# proLAYOUT.net
KiCad netlist of a schematic drawn in Altium Designer
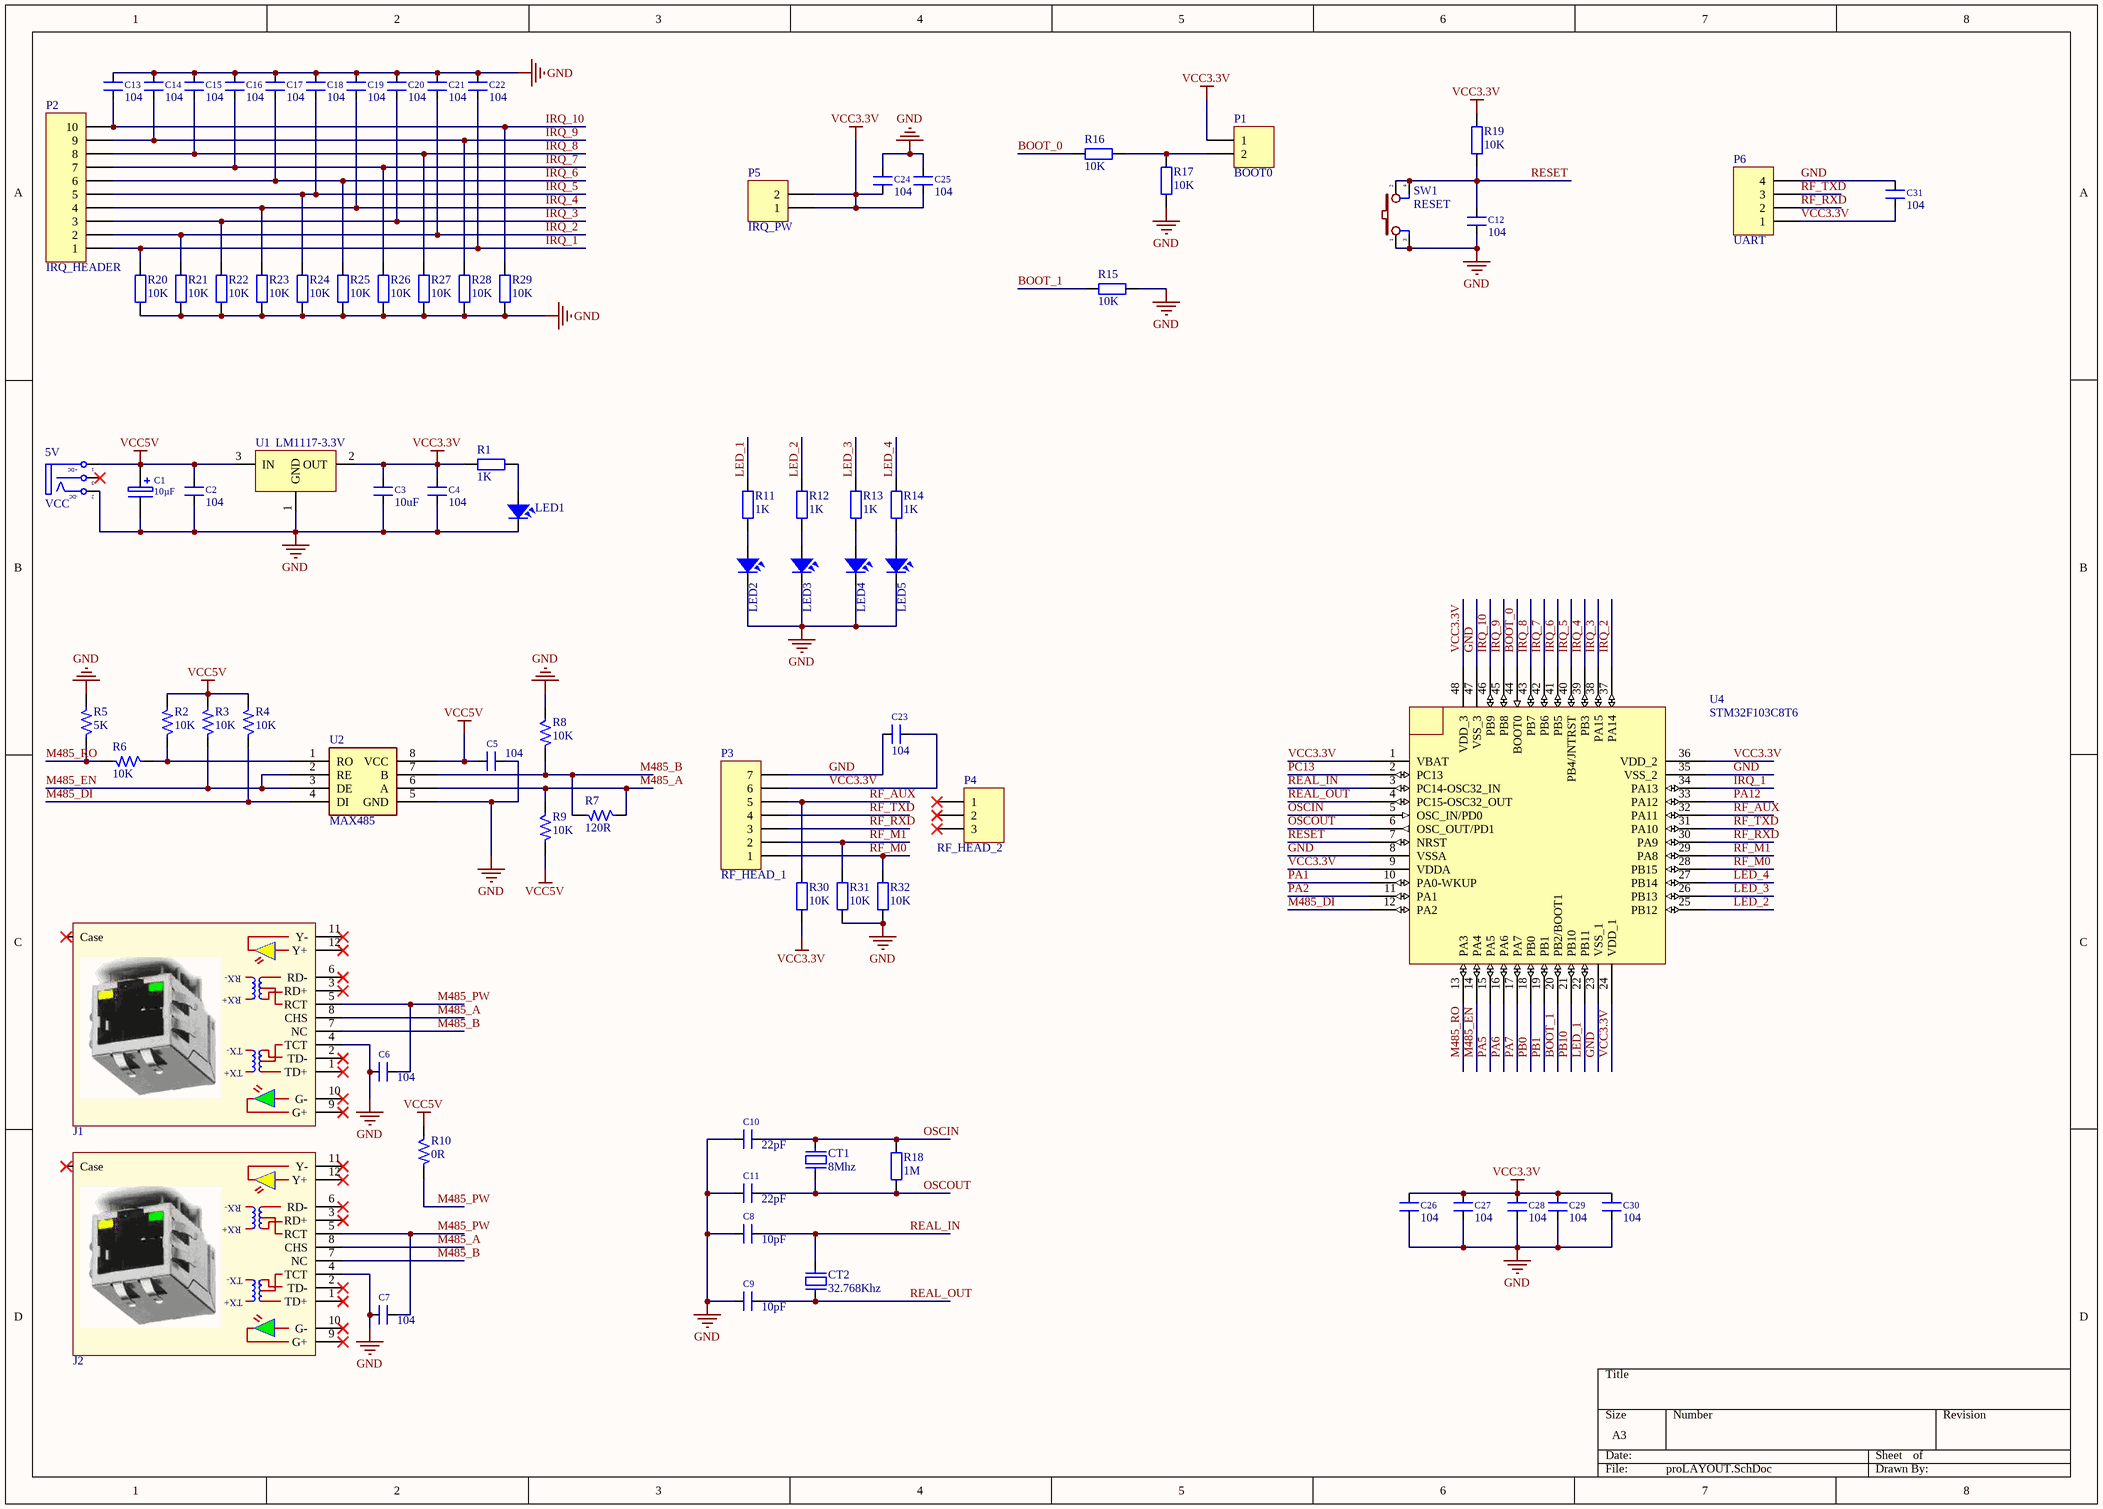
[diagram p0: proLAYOUT.SchDoc]

(export (version "E")
  (design (tool "Eeschema 10.0.6"))
  (components
    (comp (ref "C1")
      (value "10µF")
      (footprint "CAP_ELEC_5x5.7")
      (fields (field (name "ALTIUM_UNNAMED_1") "10µF"))
      (libsource (lib "My library altium") (part "CAP Aluminum"))
    )
    (comp (ref "C2")
      (value "104")
      (footprint "SM-CAP-0805")
      (fields (field (name "DESIGNED BY") "VanDungEvn"))
      (libsource (lib "My library altium") (part "CAP SMD"))
    )
    (comp (ref "C3")
      (value "10uF")
      (footprint "SM-CAP-0805")
      (fields (field (name "DESIGNED BY") "VanDungEvn"))
      (libsource (lib "My library altium") (part "CAP SMD"))
    )
    (comp (ref "C4")
      (value "104")
      (footprint "SM-CAP-0805")
      (fields (field (name "DESIGNED BY") "VanDungEvn"))
      (libsource (lib "My library altium") (part "CAP SMD"))
    )
    (comp (ref "C5")
      (value "104")
      (footprint "SM-CAP-0805")
      (fields (field (name "DESIGNED BY") "VanDungEvn"))
      (libsource (lib "My library altium") (part "CAP SMD"))
    )
    (comp (ref "C6")
      (value "104")
      (footprint "SM-CAP-0805")
      (fields (field (name "DESIGNED BY") "VanDungEvn"))
      (libsource (lib "My library altium") (part "CAP SMD"))
    )
    (comp (ref "C7")
      (value "104")
      (footprint "SM-CAP-0805")
      (fields (field (name "DESIGNED BY") "VanDungEvn"))
      (libsource (lib "My library altium") (part "CAP SMD"))
    )
    (comp (ref "C8")
      (value "10pF")
      (footprint "SM-CAP-0805")
      (fields (field (name "DESIGNED BY") "VanDungEvn"))
      (libsource (lib "My library altium") (part "CAP SMD"))
    )
    (comp (ref "C9")
      (value "10pF")
      (footprint "SM-CAP-0805")
      (fields (field (name "DESIGNED BY") "VanDungEvn"))
      (libsource (lib "My library altium") (part "CAP SMD"))
    )
    (comp (ref "C10")
      (value "22pF")
      (footprint "SM-CAP-0805")
      (fields (field (name "DESIGNED BY") "VanDungEvn"))
      (libsource (lib "My library altium") (part "CAP SMD"))
    )
    (comp (ref "C11")
      (value "22pF")
      (footprint "SM-CAP-0805")
      (fields (field (name "DESIGNED BY") "VanDungEvn"))
      (libsource (lib "My library altium") (part "CAP SMD"))
    )
    (comp (ref "C12")
      (value "104")
      (footprint "SM-CAP-0805")
      (fields (field (name "DESIGNED BY") "VanDungEvn"))
      (libsource (lib "My library altium") (part "CAP SMD"))
    )
    (comp (ref "C13")
      (value "104")
      (footprint "SM-CAP-0805")
      (fields (field (name "DESIGNED BY") "VanDungEvn"))
      (libsource (lib "My library altium") (part "CAP SMD"))
    )
    (comp (ref "C14")
      (value "104")
      (footprint "SM-CAP-0805")
      (fields (field (name "DESIGNED BY") "VanDungEvn"))
      (libsource (lib "My library altium") (part "CAP SMD"))
    )
    (comp (ref "C15")
      (value "104")
      (footprint "SM-CAP-0805")
      (fields (field (name "DESIGNED BY") "VanDungEvn"))
      (libsource (lib "My library altium") (part "CAP SMD"))
    )
    (comp (ref "C16")
      (value "104")
      (footprint "SM-CAP-0805")
      (fields (field (name "DESIGNED BY") "VanDungEvn"))
      (libsource (lib "My library altium") (part "CAP SMD"))
    )
    (comp (ref "C17")
      (value "104")
      (footprint "SM-CAP-0805")
      (fields (field (name "DESIGNED BY") "VanDungEvn"))
      (libsource (lib "My library altium") (part "CAP SMD"))
    )
    (comp (ref "C18")
      (value "104")
      (footprint "SM-CAP-0805")
      (fields (field (name "DESIGNED BY") "VanDungEvn"))
      (libsource (lib "My library altium") (part "CAP SMD"))
    )
    (comp (ref "C19")
      (value "104")
      (footprint "SM-CAP-0805")
      (fields (field (name "DESIGNED BY") "VanDungEvn"))
      (libsource (lib "My library altium") (part "CAP SMD"))
    )
    (comp (ref "C20")
      (value "104")
      (footprint "SM-CAP-0805")
      (fields (field (name "DESIGNED BY") "VanDungEvn"))
      (libsource (lib "My library altium") (part "CAP SMD"))
    )
    (comp (ref "C21")
      (value "104")
      (footprint "SM-CAP-0805")
      (fields (field (name "DESIGNED BY") "VanDungEvn"))
      (libsource (lib "My library altium") (part "CAP SMD"))
    )
    (comp (ref "C22")
      (value "104")
      (footprint "SM-CAP-0805")
      (fields (field (name "DESIGNED BY") "VanDungEvn"))
      (libsource (lib "My library altium") (part "CAP SMD"))
    )
    (comp (ref "C23")
      (value "104")
      (footprint "SM-CAP-0805")
      (fields (field (name "DESIGNED BY") "VanDungEvn"))
      (libsource (lib "My library altium") (part "CAP SMD"))
    )
    (comp (ref "C24")
      (value "104")
      (footprint "SM-CAP-0805")
      (fields (field (name "DESIGNED BY") "VanDungEvn"))
      (libsource (lib "My library altium") (part "CAP SMD"))
    )
    (comp (ref "C25")
      (value "104")
      (footprint "SM-CAP-0805")
      (fields (field (name "DESIGNED BY") "VanDungEvn"))
      (libsource (lib "My library altium") (part "CAP SMD"))
    )
    (comp (ref "C26")
      (value "104")
      (footprint "SM-CAP-0805")
      (fields (field (name "DESIGNED BY") "VanDungEvn"))
      (libsource (lib "My library altium") (part "CAP SMD"))
    )
    (comp (ref "C27")
      (value "104")
      (footprint "SM-CAP-0805")
      (fields (field (name "DESIGNED BY") "VanDungEvn"))
      (libsource (lib "My library altium") (part "CAP SMD"))
    )
    (comp (ref "C28")
      (value "104")
      (footprint "SM-CAP-0805")
      (fields (field (name "DESIGNED BY") "VanDungEvn"))
      (libsource (lib "My library altium") (part "CAP SMD"))
    )
    (comp (ref "C29")
      (value "104")
      (footprint "SM-CAP-0805")
      (fields (field (name "DESIGNED BY") "VanDungEvn"))
      (libsource (lib "My library altium") (part "CAP SMD"))
    )
    (comp (ref "C30")
      (value "104")
      (footprint "SM-CAP-0805")
      (fields (field (name "DESIGNED BY") "VanDungEvn"))
      (libsource (lib "My library altium") (part "CAP SMD"))
    )
    (comp (ref "C31")
      (value "104")
      (footprint "SM-CAP-0805")
      (fields (field (name "DESIGNED BY") "VanDungEvn"))
      (libsource (lib "My library altium") (part "CAP SMD"))
    )
    (comp (ref "CT1")
      (value "8Mhz")
      (footprint "CRYSTAL_HC49-US-SM")
      (description "Crystal For all Crystal 2pin.")
      (libsource (lib "My library altium") (part "CRYSTAL"))
    )
    (comp (ref "CT2")
      (value "32.768Khz")
      (footprint "CRYSTAL SMD 32,768 kHz")
      (description "Crystal For all Crystal 2pin.")
      (libsource (lib "My library altium") (part "CRYSTAL"))
    )
    (comp (ref "J1")
      (value "HR911105A")
      (footprint "RJ45-LED")
      (description "HR911105A Single RJ45 Connector LED")
      (libsource (lib "PART") (part "RJ45-LAN_05A"))
    )
    (comp (ref "J2")
      (value "HR911105A")
      (footprint "RJ45-LED")
      (description "HR911105A Single RJ45 Connector LED")
      (libsource (lib "PART") (part "RJ45-LAN_05A"))
    )
    (comp (ref "LED1")
      (value "LED")
      (footprint "L-0805")
      (description "LED Single colour Green and Red")
      (libsource (lib "Library AL") (part "LED"))
    )
    (comp (ref "LED2")
      (value "LED")
      (footprint "L-0805")
      (description "LED Single colour Green and Red")
      (libsource (lib "Library AL") (part "LED"))
    )
    (comp (ref "LED3")
      (value "LED")
      (footprint "L-0805")
      (description "LED Single colour Green and Red")
      (libsource (lib "Library AL") (part "LED"))
    )
    (comp (ref "LED4")
      (value "LED")
      (footprint "L-0805")
      (description "LED Single colour Green and Red")
      (libsource (lib "Library AL") (part "LED"))
    )
    (comp (ref "LED5")
      (value "LED")
      (footprint "L-0805")
      (description "LED Single colour Green and Red")
      (libsource (lib "Library AL") (part "LED"))
    )
    (comp (ref "P1")
      (value "BOOT0")
      (footprint "HDR1X2")
      (description "Header, 2-Pin")
      (fields (field (name "PUBLISHER") "Altium Limited"))
      (libsource (lib "Library AL") (part "Header 2"))
    )
    (comp (ref "P2")
      (value "IRQ_HEADER")
      (footprint "HDR1X10")
      (description "Header, 10-Pin")
      (fields (field (name "PUBLISHER") "Altium Limited"))
      (libsource (lib "Library AL") (part "Header 10"))
    )
    (comp (ref "P3")
      (value "RF_HEAD_1")
      (footprint "HDR1X7")
      (description "Header, 7-Pin")
      (fields (field (name "PUBLISHER") "Altium Limited"))
      (libsource (lib "Library AL") (part "Header 7"))
    )
    (comp (ref "P4")
      (value "RF_HEAD_2")
      (footprint "HDR1X3")
      (description "Header, 3-Pin")
      (fields (field (name "PUBLISHER") "Altium Limited"))
      (libsource (lib "Library AL") (part "Header 3"))
    )
    (comp (ref "P5")
      (value "IRQ_PW")
      (footprint "HDR1X2")
      (description "Header, 2-Pin")
      (fields (field (name "PUBLISHER") "Altium Limited"))
      (libsource (lib "") (part "Header 2_1"))
    )
    (comp (ref "P6")
      (value "UART")
      (footprint "HDR1X4")
      (description "Header, 4-Pin")
      (fields (field (name "PUBLISHER") "Altium Limited"))
      (libsource (lib "Library AL") (part "Header 4"))
    )
    (comp (ref "R1")
      (value "1K")
      (footprint "SM-0805")
      (description "Resistor SMD")
      (libsource (lib "Library AL") (part "RM"))
    )
    (comp (ref "R2")
      (value "10K")
      (footprint "R-0805")
      (description "Resistor 1/4W")
      (libsource (lib "Library AL") (part "R"))
    )
    (comp (ref "R3")
      (value "10K")
      (footprint "R-0805")
      (description "Resistor 1/4W")
      (libsource (lib "Library AL") (part "R"))
    )
    (comp (ref "R4")
      (value "10K")
      (footprint "R-0805")
      (description "Resistor 1/4W")
      (libsource (lib "Library AL") (part "R"))
    )
    (comp (ref "R5")
      (value "5K")
      (footprint "R-0805")
      (description "Resistor 1/4W")
      (libsource (lib "Library AL") (part "R"))
    )
    (comp (ref "R6")
      (value "10K")
      (footprint "R-0805")
      (description "Resistor 1/4W")
      (libsource (lib "Library AL") (part "R"))
    )
    (comp (ref "R7")
      (value "120R")
      (footprint "R-0805")
      (description "Resistor 1/4W")
      (libsource (lib "Library AL") (part "R"))
    )
    (comp (ref "R8")
      (value "10K")
      (footprint "R-0805")
      (description "Resistor 1/4W")
      (libsource (lib "Library AL") (part "R"))
    )
    (comp (ref "R9")
      (value "10K")
      (footprint "R-0805")
      (description "Resistor 1/4W")
      (libsource (lib "Library AL") (part "R"))
    )
    (comp (ref "R10")
      (value "0R")
      (footprint "R-0805")
      (description "Resistor 1/4W")
      (libsource (lib "Library AL") (part "R"))
    )
    (comp (ref "R11")
      (value "1K")
      (footprint "SM-0805")
      (description "Resistor SMD")
      (libsource (lib "Library AL") (part "RM"))
    )
    (comp (ref "R12")
      (value "1K")
      (footprint "SM-0805")
      (description "Resistor SMD")
      (libsource (lib "Library AL") (part "RM"))
    )
    (comp (ref "R13")
      (value "1K")
      (footprint "SM-0805")
      (description "Resistor SMD")
      (libsource (lib "Library AL") (part "RM"))
    )
    (comp (ref "R14")
      (value "1K")
      (footprint "SM-0805")
      (description "Resistor SMD")
      (libsource (lib "Library AL") (part "RM"))
    )
    (comp (ref "R15")
      (value "10K")
      (footprint "SM-0805")
      (description "Resistor SMD")
      (libsource (lib "Library AL") (part "RM"))
    )
    (comp (ref "R16")
      (value "10K")
      (footprint "SM-0805")
      (description "Resistor SMD")
      (libsource (lib "Library AL") (part "RM"))
    )
    (comp (ref "R17")
      (value "10K")
      (footprint "SM-0805")
      (description "Resistor SMD")
      (libsource (lib "Library AL") (part "RM"))
    )
    (comp (ref "R18")
      (value "1M")
      (footprint "SM-0805")
      (description "Resistor SMD")
      (libsource (lib "Library AL") (part "RM"))
    )
    (comp (ref "R19")
      (value "10K")
      (footprint "SM-0805")
      (description "Resistor SMD")
      (libsource (lib "Library AL") (part "RM"))
    )
    (comp (ref "R20")
      (value "10K")
      (footprint "SM-0805")
      (description "Resistor SMD")
      (libsource (lib "Library AL") (part "RM"))
    )
    (comp (ref "R21")
      (value "10K")
      (footprint "SM-0805")
      (description "Resistor SMD")
      (libsource (lib "Library AL") (part "RM"))
    )
    (comp (ref "R22")
      (value "10K")
      (footprint "SM-0805")
      (description "Resistor SMD")
      (libsource (lib "Library AL") (part "RM"))
    )
    (comp (ref "R23")
      (value "10K")
      (footprint "SM-0805")
      (description "Resistor SMD")
      (libsource (lib "Library AL") (part "RM"))
    )
    (comp (ref "R24")
      (value "10K")
      (footprint "SM-0805")
      (description "Resistor SMD")
      (libsource (lib "Library AL") (part "RM"))
    )
    (comp (ref "R25")
      (value "10K")
      (footprint "SM-0805")
      (description "Resistor SMD")
      (libsource (lib "Library AL") (part "RM"))
    )
    (comp (ref "R26")
      (value "10K")
      (footprint "SM-0805")
      (description "Resistor SMD")
      (libsource (lib "Library AL") (part "RM"))
    )
    (comp (ref "R27")
      (value "10K")
      (footprint "SM-0805")
      (description "Resistor SMD")
      (libsource (lib "Library AL") (part "RM"))
    )
    (comp (ref "R28")
      (value "10K")
      (footprint "SM-0805")
      (description "Resistor SMD")
      (libsource (lib "Library AL") (part "RM"))
    )
    (comp (ref "R29")
      (value "10K")
      (footprint "SM-0805")
      (description "Resistor SMD")
      (libsource (lib "Library AL") (part "RM"))
    )
    (comp (ref "R30")
      (value "10K")
      (footprint "SM-0805")
      (description "Resistor SMD")
      (libsource (lib "Library AL") (part "RM"))
    )
    (comp (ref "R31")
      (value "10K")
      (footprint "SM-0805")
      (description "Resistor SMD")
      (libsource (lib "Library AL") (part "RM"))
    )
    (comp (ref "R32")
      (value "10K")
      (footprint "SM-0805")
      (description "Resistor SMD")
      (libsource (lib "Library AL") (part "RM"))
    )
    (comp (ref "SW1")
      (value "RESET")
      (footprint "SW4 CMD M")
      (description "Switch button 4 pin")
      (libsource (lib "Library AL") (part "SW4-1"))
    )
    (comp (ref "U1")
      (value "LM1117-3.3V")
      (footprint "LM1117-SOP")
      (description "800mA Low-Dropout Linear Regulator")
      (fields (field (name "CREATOR") "Nguyen Ba Bien"))
      (libsource (lib "My library altium") (part "LM1117"))
    )
    (comp (ref "U2")
      (value "MAX485")
      (footprint "SO8W_N")
      (libsource (lib "My library altium") (part "max485_smd"))
    )
    (comp (ref "U4")
      (value "STM32F103C8T6")
      (footprint "STM32_LQPF48")
      (description "STM32 ARM-based 32-bit MCU with 64 Kbytes Flash, 48-pin LQFP, Industrial Temperature")
      (fields (field (name "PUBLISHER") "Altium Limited"))
      (libsource (lib "My library altium") (part "STM32F103xx_LQFP48"))
    )
    (comp (ref "VCC") (value "5V") (footprint "DC-IN") (libsource (lib "My library altium") (part "DCIN")))
  )
  (nets
    (net (code "1") (name "/BOOT_0") (class "Default")
      (node (ref "R16") (pin "2") (pinfunction "2_2") (pintype "passive"))
      (node (ref "U4") (pin "44") (pinfunction "BOOT0_44") (pintype "input"))
    )
    (net (code "2") (name "/BOOT_1") (class "Default")
      (node (ref "R15") (pin "2") (pinfunction "2_2") (pintype "passive"))
      (node (ref "U4") (pin "20") (pinfunction "PB2/BOOT1_20") (pintype "bidirectional"))
    )
    (net (code "3") (name "/IRQ_1") (class "Default")
      (node (ref "C22") (pin "1") (pinfunction "1_1") (pintype "passive"))
      (node (ref "P2") (pin "1") (pinfunction "1_1") (pintype "passive"))
      (node (ref "R20") (pin "1") (pinfunction "1_1") (pintype "passive"))
      (node (ref "U4") (pin "34") (pinfunction "PA13_34") (pintype "bidirectional"))
    )
    (net (code "4") (name "/IRQ_2") (class "Default")
      (node (ref "C21") (pin "1") (pinfunction "1_1") (pintype "passive"))
      (node (ref "P2") (pin "2") (pinfunction "2_2") (pintype "passive"))
      (node (ref "R21") (pin "1") (pinfunction "1_1") (pintype "passive"))
      (node (ref "U4") (pin "37") (pinfunction "PA14_37") (pintype "bidirectional"))
    )
    (net (code "5") (name "/IRQ_3") (class "Default")
      (node (ref "C20") (pin "1") (pinfunction "1_1") (pintype "passive"))
      (node (ref "P2") (pin "3") (pinfunction "3_3") (pintype "passive"))
      (node (ref "R22") (pin "1") (pinfunction "1_1") (pintype "passive"))
      (node (ref "U4") (pin "38") (pinfunction "PA15_38") (pintype "bidirectional"))
    )
    (net (code "6") (name "/IRQ_4") (class "Default")
      (node (ref "C19") (pin "1") (pinfunction "1_1") (pintype "passive"))
      (node (ref "P2") (pin "4") (pinfunction "4_4") (pintype "passive"))
      (node (ref "R23") (pin "1") (pinfunction "1_1") (pintype "passive"))
      (node (ref "U4") (pin "39") (pinfunction "PB3_39") (pintype "bidirectional"))
    )
    (net (code "7") (name "/IRQ_5") (class "Default")
      (node (ref "C18") (pin "1") (pinfunction "1_1") (pintype "passive"))
      (node (ref "P2") (pin "5") (pinfunction "5_5") (pintype "passive"))
      (node (ref "R24") (pin "1") (pinfunction "1_1") (pintype "passive"))
      (node (ref "U4") (pin "40") (pinfunction "PB4/JNTRST_40") (pintype "bidirectional"))
    )
    (net (code "8") (name "/IRQ_6") (class "Default")
      (node (ref "C17") (pin "1") (pinfunction "1_1") (pintype "passive"))
      (node (ref "P2") (pin "6") (pinfunction "6_6") (pintype "passive"))
      (node (ref "R25") (pin "1") (pinfunction "1_1") (pintype "passive"))
      (node (ref "U4") (pin "41") (pinfunction "PB5_41") (pintype "bidirectional"))
    )
    (net (code "9") (name "/IRQ_7") (class "Default")
      (node (ref "C16") (pin "1") (pinfunction "1_1") (pintype "passive"))
      (node (ref "P2") (pin "7") (pinfunction "7_7") (pintype "passive"))
      (node (ref "R26") (pin "1") (pinfunction "1_1") (pintype "passive"))
      (node (ref "U4") (pin "42") (pinfunction "PB6_42") (pintype "bidirectional"))
    )
    (net (code "10") (name "/IRQ_8") (class "Default")
      (node (ref "C15") (pin "1") (pinfunction "1_1") (pintype "passive"))
      (node (ref "P2") (pin "8") (pinfunction "8_8") (pintype "passive"))
      (node (ref "R27") (pin "1") (pinfunction "1_1") (pintype "passive"))
      (node (ref "U4") (pin "43") (pinfunction "PB7_43") (pintype "bidirectional"))
    )
    (net (code "11") (name "/IRQ_9") (class "Default")
      (node (ref "C14") (pin "1") (pinfunction "1_1") (pintype "passive"))
      (node (ref "P2") (pin "9") (pinfunction "9_9") (pintype "passive"))
      (node (ref "R28") (pin "1") (pinfunction "1_1") (pintype "passive"))
      (node (ref "U4") (pin "45") (pinfunction "PB8_45") (pintype "bidirectional"))
    )
    (net (code "12") (name "/IRQ_10") (class "Default")
      (node (ref "C13") (pin "1") (pinfunction "1_1") (pintype "passive"))
      (node (ref "P2") (pin "10") (pinfunction "10_10") (pintype "passive"))
      (node (ref "R29") (pin "1") (pinfunction "1_1") (pintype "passive"))
      (node (ref "U4") (pin "46") (pinfunction "PB9_46") (pintype "bidirectional"))
    )
    (net (code "13") (name "/LED_1") (class "Default")
      (node (ref "R11") (pin "2") (pinfunction "2_2") (pintype "passive"))
      (node (ref "U4") (pin "22") (pinfunction "PB11_22") (pintype "bidirectional"))
    )
    (net (code "14") (name "/LED_2") (class "Default")
      (node (ref "R12") (pin "2") (pinfunction "2_2") (pintype "passive"))
      (node (ref "U4") (pin "25") (pinfunction "PB12_25") (pintype "bidirectional"))
    )
    (net (code "15") (name "/LED_3") (class "Default")
      (node (ref "R13") (pin "2") (pinfunction "2_2") (pintype "passive"))
      (node (ref "U4") (pin "26") (pinfunction "PB13_26") (pintype "bidirectional"))
    )
    (net (code "16") (name "/LED_4") (class "Default")
      (node (ref "R14") (pin "2") (pinfunction "2_2") (pintype "passive"))
      (node (ref "U4") (pin "27") (pinfunction "PB14_27") (pintype "bidirectional"))
    )
    (net (code "17") (name "/M485_A") (class "Default")
      (node (ref "J1") (pin "8") (pinfunction "CHS_8") (pintype "passive"))
      (node (ref "J2") (pin "8") (pinfunction "CHS_8") (pintype "passive"))
      (node (ref "R7") (pin "1") (pinfunction "1_1") (pintype "passive"))
      (node (ref "R9") (pin "1") (pinfunction "1_1") (pintype "passive"))
      (node (ref "U2") (pin "6") (pinfunction "A_6") (pintype "passive"))
    )
    (net (code "18") (name "/M485_B") (class "Default")
      (node (ref "J1") (pin "7") (pinfunction "NC_7") (pintype "passive"))
      (node (ref "J2") (pin "7") (pinfunction "NC_7") (pintype "passive"))
      (node (ref "R7") (pin "2") (pinfunction "2_2") (pintype "passive"))
      (node (ref "R8") (pin "2") (pinfunction "2_2") (pintype "passive"))
      (node (ref "U2") (pin "7") (pinfunction "B_7") (pintype "passive"))
    )
    (net (code "19") (name "/M485_DI") (class "Default")
      (node (ref "R4") (pin "1") (pinfunction "1_1") (pintype "passive"))
      (node (ref "U2") (pin "4") (pinfunction "DI_4") (pintype "passive"))
      (node (ref "U4") (pin "12") (pinfunction "PA2_12") (pintype "bidirectional"))
    )
    (net (code "20") (name "/M485_EN") (class "Default")
      (node (ref "R3") (pin "1") (pinfunction "1_1") (pintype "passive"))
      (node (ref "U2") (pin "2") (pinfunction "RE_2") (pintype "passive"))
      (node (ref "U2") (pin "3") (pinfunction "DE_3") (pintype "passive"))
      (node (ref "U4") (pin "14") (pinfunction "PA4_14") (pintype "bidirectional"))
    )
    (net (code "21") (name "/M485_PW") (class "Default")
      (node (ref "C6") (pin "2") (pinfunction "2_2") (pintype "passive"))
      (node (ref "C7") (pin "2") (pinfunction "2_2") (pintype "passive"))
      (node (ref "J1") (pin "5") (pinfunction "RCT_5") (pintype "passive"))
      (node (ref "J2") (pin "5") (pinfunction "RCT_5") (pintype "passive"))
      (node (ref "R10") (pin "2") (pinfunction "2_2") (pintype "passive"))
    )
    (net (code "22") (name "/M485_RO") (class "Default")
      (node (ref "R5") (pin "1") (pinfunction "1_1") (pintype "passive"))
      (node (ref "R6") (pin "2") (pinfunction "2_2") (pintype "passive"))
      (node (ref "U4") (pin "13") (pinfunction "PA3_13") (pintype "bidirectional"))
    )
    (net (code "23") (name "/OSCIN") (class "Default")
      (node (ref "C10") (pin "2") (pinfunction "2_2") (pintype "passive"))
      (node (ref "CT1") (pin "2") (pinfunction "2_2") (pintype "passive"))
      (node (ref "R18") (pin "1") (pinfunction "1_1") (pintype "passive"))
      (node (ref "U4") (pin "5") (pinfunction "OSC_IN/PD0_5") (pintype "input"))
    )
    (net (code "24") (name "/OSCOUT") (class "Default")
      (node (ref "C11") (pin "2") (pinfunction "2_2") (pintype "passive"))
      (node (ref "CT1") (pin "1") (pinfunction "1_1") (pintype "passive"))
      (node (ref "R18") (pin "2") (pinfunction "2_2") (pintype "passive"))
      (node (ref "U4") (pin "6") (pinfunction "OSC_OUT/PD1_6") (pintype "output"))
    )
    (net (code "25") (name "/PA1") (class "Default")
      (node (ref "U4") (pin "10") (pinfunction "PA0-WKUP_10") (pintype "bidirectional"))
    )
    (net (code "26") (name "/PA2") (class "Default")
      (node (ref "U4") (pin "11") (pinfunction "PA1_11") (pintype "bidirectional"))
    )
    (net (code "27") (name "/PA5") (class "Default")
      (node (ref "U4") (pin "15") (pinfunction "PA5_15") (pintype "bidirectional"))
    )
    (net (code "28") (name "/PA6") (class "Default")
      (node (ref "U4") (pin "16") (pinfunction "PA6_16") (pintype "bidirectional"))
    )
    (net (code "29") (name "/PA7") (class "Default")
      (node (ref "U4") (pin "17") (pinfunction "PA7_17") (pintype "bidirectional"))
    )
    (net (code "30") (name "/PA12") (class "Default")
      (node (ref "U4") (pin "33") (pinfunction "PA12_33") (pintype "bidirectional"))
    )
    (net (code "31") (name "/PB0") (class "Default")
      (node (ref "U4") (pin "18") (pinfunction "PB0_18") (pintype "bidirectional"))
    )
    (net (code "32") (name "/PB1") (class "Default")
      (node (ref "U4") (pin "19") (pinfunction "PB1_19") (pintype "bidirectional"))
    )
    (net (code "33") (name "/PB10") (class "Default")
      (node (ref "U4") (pin "21") (pinfunction "PB10_21") (pintype "bidirectional"))
    )
    (net (code "34") (name "/PC13") (class "Default")
      (node (ref "U4") (pin "2") (pinfunction "PC13_2") (pintype "bidirectional"))
    )
    (net (code "35") (name "/REAL_IN") (class "Default")
      (node (ref "C8") (pin "2") (pinfunction "2_2") (pintype "passive"))
      (node (ref "CT2") (pin "2") (pinfunction "2_2") (pintype "passive"))
      (node (ref "U4") (pin "3") (pinfunction "PC14-OSC32_IN_3") (pintype "bidirectional"))
    )
    (net (code "36") (name "/REAL_OUT") (class "Default")
      (node (ref "C9") (pin "2") (pinfunction "2_2") (pintype "passive"))
      (node (ref "CT2") (pin "1") (pinfunction "1_1") (pintype "passive"))
      (node (ref "U4") (pin "4") (pinfunction "PC15-OSC32_OUT_4") (pintype "bidirectional"))
    )
    (net (code "37") (name "/RESET") (class "Default")
      (node (ref "C12") (pin "2") (pinfunction "2_2") (pintype "passive"))
      (node (ref "R19") (pin "2") (pinfunction "2_2") (pintype "passive"))
      (node (ref "SW1") (pin "2") (pinfunction "2_2") (pintype "passive"))
      (node (ref "SW1") (pin "4") (pinfunction "4_4") (pintype "passive"))
      (node (ref "U4") (pin "7") (pinfunction "NRST_7") (pintype "bidirectional"))
    )
    (net (code "38") (name "/RF_AUX") (class "Default")
      (node (ref "P3") (pin "5") (pinfunction "5_5") (pintype "passive"))
      (node (ref "R30") (pin "1") (pinfunction "1_1") (pintype "passive"))
      (node (ref "U4") (pin "32") (pinfunction "PA11_32") (pintype "bidirectional"))
    )
    (net (code "39") (name "/RF_M0") (class "Default")
      (node (ref "P3") (pin "1") (pinfunction "1_1") (pintype "passive"))
      (node (ref "R32") (pin "1") (pinfunction "1_1") (pintype "passive"))
      (node (ref "U4") (pin "28") (pinfunction "PB15_28") (pintype "bidirectional"))
    )
    (net (code "40") (name "/RF_M1") (class "Default")
      (node (ref "P3") (pin "2") (pinfunction "2_2") (pintype "passive"))
      (node (ref "R31") (pin "1") (pinfunction "1_1") (pintype "passive"))
      (node (ref "U4") (pin "29") (pinfunction "PA8_29") (pintype "bidirectional"))
    )
    (net (code "41") (name "/RF_RXD") (class "Default")
      (node (ref "P3") (pin "3") (pinfunction "3_3") (pintype "passive"))
      (node (ref "P6") (pin "2") (pinfunction "2_2") (pintype "passive"))
      (node (ref "U4") (pin "30") (pinfunction "PA9_30") (pintype "bidirectional"))
    )
    (net (code "42") (name "/RF_TXD") (class "Default")
      (node (ref "P3") (pin "4") (pinfunction "4_4") (pintype "passive"))
      (node (ref "P6") (pin "3") (pinfunction "3_3") (pintype "passive"))
      (node (ref "U4") (pin "31") (pinfunction "PA10_31") (pintype "bidirectional"))
    )
    (net (code "43") (name "GND") (class "Default")
      (node (ref "C1") (pin "2") (pintype "passive"))
      (node (ref "C10") (pin "1") (pinfunction "1_1") (pintype "passive"))
      (node (ref "C11") (pin "1") (pinfunction "1_1") (pintype "passive"))
      (node (ref "C12") (pin "1") (pinfunction "1_1") (pintype "passive"))
      (node (ref "C13") (pin "2") (pinfunction "2_2") (pintype "passive"))
      (node (ref "C14") (pin "2") (pinfunction "2_2") (pintype "passive"))
      (node (ref "C15") (pin "2") (pinfunction "2_2") (pintype "passive"))
      (node (ref "C16") (pin "2") (pinfunction "2_2") (pintype "passive"))
      (node (ref "C17") (pin "2") (pinfunction "2_2") (pintype "passive"))
      (node (ref "C18") (pin "2") (pinfunction "2_2") (pintype "passive"))
      (node (ref "C19") (pin "2") (pinfunction "2_2") (pintype "passive"))
      (node (ref "C2") (pin "1") (pinfunction "1_1") (pintype "passive"))
      (node (ref "C20") (pin "2") (pinfunction "2_2") (pintype "passive"))
      (node (ref "C21") (pin "2") (pinfunction "2_2") (pintype "passive"))
      (node (ref "C22") (pin "2") (pinfunction "2_2") (pintype "passive"))
      (node (ref "C23") (pin "2") (pinfunction "2_2") (pintype "passive"))
      (node (ref "C24") (pin "1") (pinfunction "1_1") (pintype "passive"))
      (node (ref "C25") (pin "1") (pinfunction "1_1") (pintype "passive"))
      (node (ref "C26") (pin "2") (pinfunction "2_2") (pintype "passive"))
      (node (ref "C27") (pin "2") (pinfunction "2_2") (pintype "passive"))
      (node (ref "C28") (pin "2") (pinfunction "2_2") (pintype "passive"))
      (node (ref "C29") (pin "2") (pinfunction "2_2") (pintype "passive"))
      (node (ref "C3") (pin "1") (pinfunction "1_1") (pintype "passive"))
      (node (ref "C30") (pin "2") (pinfunction "2_2") (pintype "passive"))
      (node (ref "C31") (pin "2") (pinfunction "2_2") (pintype "passive"))
      (node (ref "C4") (pin "1") (pinfunction "1_1") (pintype "passive"))
      (node (ref "C5") (pin "2") (pinfunction "2_2") (pintype "passive"))
      (node (ref "C6") (pin "1") (pinfunction "1_1") (pintype "passive"))
      (node (ref "C7") (pin "1") (pinfunction "1_1") (pintype "passive"))
      (node (ref "C8") (pin "1") (pinfunction "1_1") (pintype "passive"))
      (node (ref "C9") (pin "1") (pinfunction "1_1") (pintype "passive"))
      (node (ref "J1") (pin "4") (pinfunction "TCT_4") (pintype "passive"))
      (node (ref "J2") (pin "4") (pinfunction "TCT_4") (pintype "passive"))
      (node (ref "LED1") (pin "2") (pinfunction "2_2") (pintype "passive"))
      (node (ref "LED2") (pin "2") (pinfunction "2_2") (pintype "passive"))
      (node (ref "LED3") (pin "2") (pinfunction "2_2") (pintype "passive"))
      (node (ref "LED4") (pin "2") (pinfunction "2_2") (pintype "passive"))
      (node (ref "LED5") (pin "2") (pinfunction "2_2") (pintype "passive"))
      (node (ref "P3") (pin "7") (pinfunction "7_7") (pintype "passive"))
      (node (ref "P6") (pin "4") (pinfunction "4_4") (pintype "passive"))
      (node (ref "R15") (pin "1") (pinfunction "1_1") (pintype "passive"))
      (node (ref "R17") (pin "2") (pinfunction "2_2") (pintype "passive"))
      (node (ref "R20") (pin "2") (pinfunction "2_2") (pintype "passive"))
      (node (ref "R21") (pin "2") (pinfunction "2_2") (pintype "passive"))
      (node (ref "R22") (pin "2") (pinfunction "2_2") (pintype "passive"))
      (node (ref "R23") (pin "2") (pinfunction "2_2") (pintype "passive"))
      (node (ref "R24") (pin "2") (pinfunction "2_2") (pintype "passive"))
      (node (ref "R25") (pin "2") (pinfunction "2_2") (pintype "passive"))
      (node (ref "R26") (pin "2") (pinfunction "2_2") (pintype "passive"))
      (node (ref "R27") (pin "2") (pinfunction "2_2") (pintype "passive"))
      (node (ref "R28") (pin "2") (pinfunction "2_2") (pintype "passive"))
      (node (ref "R29") (pin "2") (pinfunction "2_2") (pintype "passive"))
      (node (ref "R31") (pin "2") (pinfunction "2_2") (pintype "passive"))
      (node (ref "R32") (pin "2") (pinfunction "2_2") (pintype "passive"))
      (node (ref "R5") (pin "2") (pinfunction "2_2") (pintype "passive"))
      (node (ref "R8") (pin "1") (pinfunction "1_1") (pintype "passive"))
      (node (ref "SW1") (pin "1") (pinfunction "1_1") (pintype "passive"))
      (node (ref "SW1") (pin "3") (pinfunction "3_3") (pintype "passive"))
      (node (ref "U1") (pin "1") (pinfunction "GND_1") (pintype "passive"))
      (node (ref "U2") (pin "5") (pinfunction "GND_5") (pintype "passive"))
      (node (ref "U4") (pin "23") (pinfunction "VSS_1_23") (pintype "power_in"))
      (node (ref "U4") (pin "35") (pinfunction "VSS_2_35") (pintype "power_in"))
      (node (ref "U4") (pin "47") (pinfunction "VSS_3_47") (pintype "power_in"))
      (node (ref "U4") (pin "8") (pinfunction "VSSA_8") (pintype "power_in"))
      (node (ref "VCC") (pin "2") (pinfunction "TN_2") (pintype "passive"))
    )
    (net (code "44") (name "Net-(LED1-Pad1)") (class "Default")
      (node (ref "LED1") (pin "1") (pinfunction "1_1") (pintype "passive"))
      (node (ref "R1") (pin "2") (pinfunction "2_2") (pintype "passive"))
    )
    (net (code "45") (name "Net-(LED2-Pad1)") (class "Default")
      (node (ref "LED2") (pin "1") (pinfunction "1_1") (pintype "passive"))
      (node (ref "R11") (pin "1") (pinfunction "1_1") (pintype "passive"))
    )
    (net (code "46") (name "Net-(LED3-Pad1)") (class "Default")
      (node (ref "LED3") (pin "1") (pinfunction "1_1") (pintype "passive"))
      (node (ref "R12") (pin "1") (pinfunction "1_1") (pintype "passive"))
    )
    (net (code "47") (name "Net-(LED4-Pad1)") (class "Default")
      (node (ref "LED4") (pin "1") (pinfunction "1_1") (pintype "passive"))
      (node (ref "R13") (pin "1") (pinfunction "1_1") (pintype "passive"))
    )
    (net (code "48") (name "Net-(LED5-Pad1)") (class "Default")
      (node (ref "LED5") (pin "1") (pinfunction "1_1") (pintype "passive"))
      (node (ref "R14") (pin "1") (pinfunction "1_1") (pintype "passive"))
    )
    (net (code "49") (name "Net-(P1-Pad2)") (class "Default")
      (node (ref "P1") (pin "2") (pinfunction "2_2") (pintype "passive"))
      (node (ref "R16") (pin "1") (pinfunction "1_1") (pintype "passive"))
      (node (ref "R17") (pin "1") (pinfunction "1_1") (pintype "passive"))
    )
    (net (code "50") (name "Net-(U2-RO)") (class "Default")
      (node (ref "R2") (pin "1") (pinfunction "1_1") (pintype "passive"))
      (node (ref "R6") (pin "1") (pinfunction "1_1") (pintype "passive"))
      (node (ref "U2") (pin "1") (pinfunction "RO_1") (pintype "passive"))
    )
    (net (code "51") (name "VCC3.3V") (class "Default")
      (node (ref "C23") (pin "1") (pinfunction "1_1") (pintype "passive"))
      (node (ref "C24") (pin "2") (pinfunction "2_2") (pintype "passive"))
      (node (ref "C25") (pin "2") (pinfunction "2_2") (pintype "passive"))
      (node (ref "C26") (pin "1") (pinfunction "1_1") (pintype "passive"))
      (node (ref "C27") (pin "1") (pinfunction "1_1") (pintype "passive"))
      (node (ref "C28") (pin "1") (pinfunction "1_1") (pintype "passive"))
      (node (ref "C29") (pin "1") (pinfunction "1_1") (pintype "passive"))
      (node (ref "C3") (pin "2") (pinfunction "2_2") (pintype "passive"))
      (node (ref "C30") (pin "1") (pinfunction "1_1") (pintype "passive"))
      (node (ref "C31") (pin "1") (pinfunction "1_1") (pintype "passive"))
      (node (ref "C4") (pin "2") (pinfunction "2_2") (pintype "passive"))
      (node (ref "P1") (pin "1") (pinfunction "1_1") (pintype "passive"))
      (node (ref "P3") (pin "6") (pinfunction "6_6") (pintype "passive"))
      (node (ref "P5") (pin "1") (pinfunction "1_1") (pintype "passive"))
      (node (ref "P5") (pin "2") (pinfunction "2_2") (pintype "passive"))
      (node (ref "P6") (pin "1") (pinfunction "1_1") (pintype "passive"))
      (node (ref "R1") (pin "1") (pinfunction "1_1") (pintype "passive"))
      (node (ref "R19") (pin "1") (pinfunction "1_1") (pintype "passive"))
      (node (ref "R30") (pin "2") (pinfunction "2_2") (pintype "passive"))
      (node (ref "U1") (pin "2") (pinfunction "OUT_2") (pintype "passive"))
      (node (ref "U4") (pin "1") (pinfunction "VBAT_1") (pintype "power_in"))
      (node (ref "U4") (pin "24") (pinfunction "VDD_1_24") (pintype "power_in"))
      (node (ref "U4") (pin "36") (pinfunction "VDD_2_36") (pintype "power_in"))
      (node (ref "U4") (pin "48") (pinfunction "VDD_3_48") (pintype "power_in"))
      (node (ref "U4") (pin "9") (pinfunction "VDDA_9") (pintype "power_in"))
    )
    (net (code "52") (name "VCC5V") (class "Default")
      (node (ref "C1") (pin "1") (pintype "passive"))
      (node (ref "C2") (pin "2") (pinfunction "2_2") (pintype "passive"))
      (node (ref "C5") (pin "1") (pinfunction "1_1") (pintype "passive"))
      (node (ref "R10") (pin "1") (pinfunction "1_1") (pintype "passive"))
      (node (ref "R2") (pin "2") (pinfunction "2_2") (pintype "passive"))
      (node (ref "R3") (pin "2") (pinfunction "2_2") (pintype "passive"))
      (node (ref "R4") (pin "2") (pinfunction "2_2") (pintype "passive"))
      (node (ref "R9") (pin "2") (pinfunction "2_2") (pintype "passive"))
      (node (ref "U1") (pin "3") (pinfunction "IN_3") (pintype "passive"))
      (node (ref "U2") (pin "8") (pinfunction "VCC_8") (pintype "passive"))
      (node (ref "VCC") (pin "1") (pinfunction "T_1") (pintype "passive"))
    )
    (net (code "53") (name "unconnected-(J1-Case-Pad0)") (class "Default")
      (node (ref "J1") (pin "0") (pinfunction "Case_0") (pintype "passive+no_connect"))
    )
    (net (code "54") (name "unconnected-(J1-G+-Pad9)") (class "Default")
      (node (ref "J1") (pin "9") (pinfunction "G+_9") (pintype "passive+no_connect"))
    )
    (net (code "55") (name "unconnected-(J1-G--Pad10)") (class "Default")
      (node (ref "J1") (pin "10") (pinfunction "G-_10") (pintype "passive+no_connect"))
    )
    (net (code "56") (name "unconnected-(J1-RD+-Pad3)") (class "Default")
      (node (ref "J1") (pin "3") (pinfunction "RD+_3") (pintype "passive+no_connect"))
    )
    (net (code "57") (name "unconnected-(J1-RD--Pad6)") (class "Default")
      (node (ref "J1") (pin "6") (pinfunction "RD-_6") (pintype "passive+no_connect"))
    )
    (net (code "58") (name "unconnected-(J1-TD+-Pad1)") (class "Default")
      (node (ref "J1") (pin "1") (pinfunction "TD+_1") (pintype "passive+no_connect"))
    )
    (net (code "59") (name "unconnected-(J1-TD--Pad2)") (class "Default")
      (node (ref "J1") (pin "2") (pinfunction "TD-_2") (pintype "passive+no_connect"))
    )
    (net (code "60") (name "unconnected-(J1-Y+-Pad12)") (class "Default")
      (node (ref "J1") (pin "12") (pinfunction "Y+_12") (pintype "passive+no_connect"))
    )
    (net (code "61") (name "unconnected-(J1-Y--Pad11)") (class "Default")
      (node (ref "J1") (pin "11") (pinfunction "Y-_11") (pintype "passive+no_connect"))
    )
    (net (code "62") (name "unconnected-(J2-Case-Pad0)") (class "Default")
      (node (ref "J2") (pin "0") (pinfunction "Case_0") (pintype "passive+no_connect"))
    )
    (net (code "63") (name "unconnected-(J2-G+-Pad9)") (class "Default")
      (node (ref "J2") (pin "9") (pinfunction "G+_9") (pintype "passive+no_connect"))
    )
    (net (code "64") (name "unconnected-(J2-G--Pad10)") (class "Default")
      (node (ref "J2") (pin "10") (pinfunction "G-_10") (pintype "passive+no_connect"))
    )
    (net (code "65") (name "unconnected-(J2-RD+-Pad3)") (class "Default")
      (node (ref "J2") (pin "3") (pinfunction "RD+_3") (pintype "passive+no_connect"))
    )
    (net (code "66") (name "unconnected-(J2-RD--Pad6)") (class "Default")
      (node (ref "J2") (pin "6") (pinfunction "RD-_6") (pintype "passive+no_connect"))
    )
    (net (code "67") (name "unconnected-(J2-TD+-Pad1)") (class "Default")
      (node (ref "J2") (pin "1") (pinfunction "TD+_1") (pintype "passive+no_connect"))
    )
    (net (code "68") (name "unconnected-(J2-TD--Pad2)") (class "Default")
      (node (ref "J2") (pin "2") (pinfunction "TD-_2") (pintype "passive+no_connect"))
    )
    (net (code "69") (name "unconnected-(J2-Y+-Pad12)") (class "Default")
      (node (ref "J2") (pin "12") (pinfunction "Y+_12") (pintype "passive+no_connect"))
    )
    (net (code "70") (name "unconnected-(J2-Y--Pad11)") (class "Default")
      (node (ref "J2") (pin "11") (pinfunction "Y-_11") (pintype "passive+no_connect"))
    )
    (net (code "71") (name "unconnected-(P4-Pad1)") (class "Default")
      (node (ref "P4") (pin "1") (pinfunction "1_1") (pintype "passive+no_connect"))
    )
    (net (code "72") (name "unconnected-(P4-Pad2)") (class "Default")
      (node (ref "P4") (pin "2") (pinfunction "2_2") (pintype "passive+no_connect"))
    )
    (net (code "73") (name "unconnected-(P4-Pad3)") (class "Default")
      (node (ref "P4") (pin "3") (pinfunction "3_3") (pintype "passive+no_connect"))
    )
    (net (code "74") (name "unconnected-(VCC-S-Pad3)") (class "Default")
      (node (ref "VCC") (pin "3") (pinfunction "S_3") (pintype "power_in+no_connect"))
    )
  )
)
